# MB1297_MCU2.net
KiCad netlist of a schematic drawn in Altium Designer
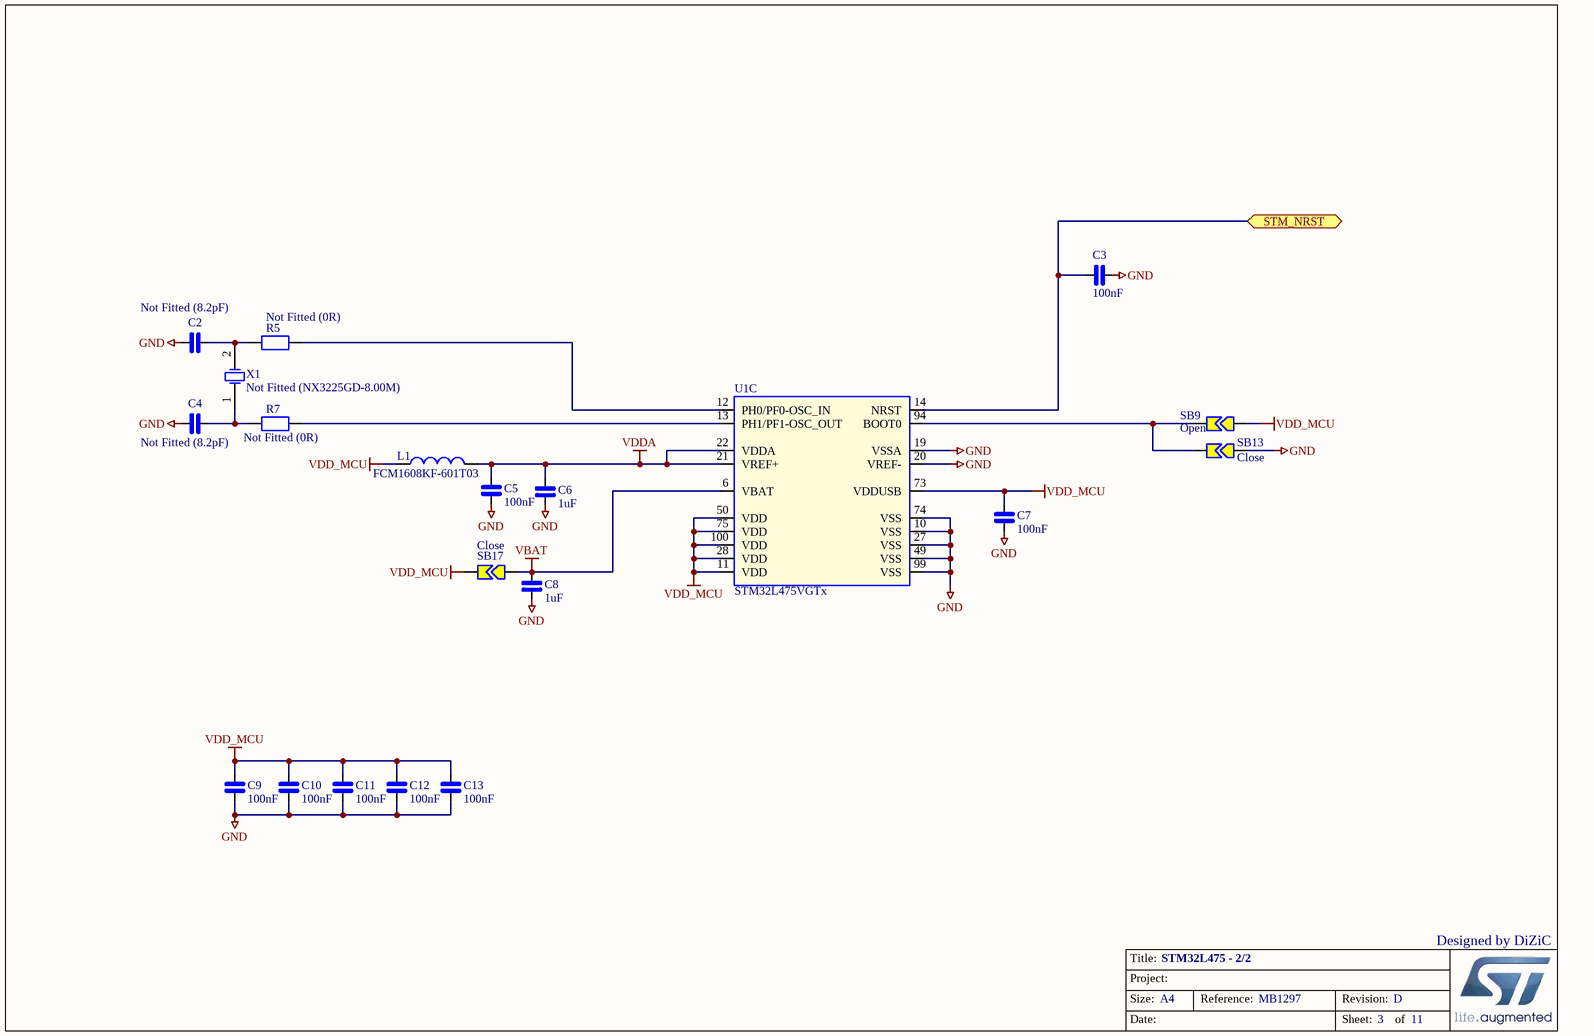
[diagram p0: MB1297_MCU2.SchDoc]

(export (version "E")
  (design (tool "Eeschema 10.0.6"))
  (components
    (comp (ref "C2")
      (value "Not Fitted (8.2pF)")
      (footprint "0402_CAP_NPOL")
      (description "Capacitor_not polarized")
      (libsource (lib "ST_Lib3D") (part "CAP_NPOL"))
    )
    (comp (ref "C3")
      (value "100nF")
      (footprint "0402_CAP_NPOL")
      (description "Capacitor_not polarized")
      (libsource (lib "ST_Lib3D") (part "CAP_NPOL"))
    )
    (comp (ref "C4")
      (value "Not Fitted (8.2pF)")
      (footprint "0402_CAP_NPOL")
      (description "Capacitor_not polarized")
      (libsource (lib "ST_Lib3D") (part "CAP_NPOL"))
    )
    (comp (ref "C5")
      (value "100nF")
      (footprint "0402_CAP_NPOL")
      (description "Capacitor_not polarized")
      (libsource (lib "ST_Lib3D") (part "CAP_NPOL"))
    )
    (comp (ref "C6")
      (value "1uF")
      (footprint "0402_CAP_NPOL")
      (description "Capacitor_not polarized")
      (libsource (lib "ST_Lib3D") (part "CAP_NPOL"))
    )
    (comp (ref "C7")
      (value "100nF")
      (footprint "0402_CAP_NPOL")
      (description "Capacitor_not polarized")
      (libsource (lib "ST_Lib3D") (part "CAP_NPOL"))
    )
    (comp (ref "C8")
      (value "1uF")
      (footprint "0402_CAP_NPOL")
      (description "Capacitor_not polarized")
      (libsource (lib "ST_Lib3D") (part "CAP_NPOL"))
    )
    (comp (ref "C9")
      (value "100nF")
      (footprint "0402_CAP_NPOL")
      (description "Capacitor_not polarized")
      (libsource (lib "MB1297") (part "CAP_NPOL"))
    )
    (comp (ref "C10")
      (value "100nF")
      (footprint "0402_CAP_NPOL")
      (description "Capacitor_not polarized")
      (libsource (lib "MB1297") (part "CAP_NPOL"))
    )
    (comp (ref "C11")
      (value "100nF")
      (footprint "0402_CAP_NPOL")
      (description "Capacitor_not polarized")
      (libsource (lib "MB1297") (part "CAP_NPOL"))
    )
    (comp (ref "C12")
      (value "100nF")
      (footprint "0402_CAP_NPOL")
      (description "Capacitor_not polarized")
      (libsource (lib "MB1297") (part "CAP_NPOL"))
    )
    (comp (ref "C13")
      (value "100nF")
      (footprint "0402_CAP_NPOL")
      (description "Capacitor_not polarized")
      (libsource (lib "MB1297") (part "CAP_NPOL"))
    )
    (comp (ref "L1")
      (value "FCM1608KF-601T03")
      (footprint "0603L")
      (description "Inductor")
      (fields (field (name "PUBLISHER") "Altium Limited"))
      (libsource (lib "Miscellaneous Devices") (part "Inductor"))
    )
    (comp (ref "R5")
      (value "Not Fitted (0R)")
      (footprint "0402_RES")
      (description "Resistor")
      (libsource (lib "Lib3D_Altium10_Schlib") (part "RES"))
    )
    (comp (ref "R7")
      (value "Not Fitted (0R)")
      (footprint "0402_RES")
      (description "Resistor")
      (libsource (lib "Lib3D_Altium10_Schlib") (part "RES"))
    )
    (comp (ref "SB9")
      (value "Open")
      (footprint "SB")
      (description "Solder Jumper")
      (fields (field (name "PUBLISHER") "Altium Limited"))
      (libsource (lib "ST_Lib3D") (part "Strap2"))
    )
    (comp (ref "SB13")
      (value "Close")
      (footprint "SB")
      (description "Solder Jumper")
      (fields (field (name "PUBLISHER") "Altium Limited"))
      (libsource (lib "ST_Lib3D") (part "Strap2"))
    )
    (comp (ref "SB17")
      (value "Close")
      (footprint "SB")
      (description "Solder Jumper")
      (fields (field (name "PUBLISHER") "Altium Limited"))
      (libsource (lib "Lib3D_Altium10_Schlib") (part "Strap2"))
    )
    (comp (ref "U1")
      (value "STM32L475VGTx")
      (footprint "LQFP100 14x14x1.6")
      (libsource (lib "ST_Lib3D") (part "STM32L475VGTx"))
    )
    (comp (ref "X1")
      (value "Not Fitted (NX3225GD-8.00M)")
      (footprint "CRY_NX3225GD_2P")
      (description "Crystal 8Mhz, 8pF, -+50PPM, SMD")
      (libsource (lib "MCD_TEMP_PCH") (part "XTAL_8M_NX3225GD"))
    )
  )
  (nets
    (net (code "1") (name "/STM_NRST") (class "Default")
      (node (ref "C3") (pin "2") (pinfunction "2_2") (pintype "passive"))
      (node (ref "U1") (pin "14") (pinfunction "NRST_14") (pintype "passive"))
    )
    (net (code "2") (name "GND") (class "Default")
      (node (ref "C10") (pin "2") (pinfunction "2_2") (pintype "passive"))
      (node (ref "C11") (pin "2") (pinfunction "2_2") (pintype "passive"))
      (node (ref "C12") (pin "2") (pinfunction "2_2") (pintype "passive"))
      (node (ref "C13") (pin "2") (pinfunction "2_2") (pintype "passive"))
      (node (ref "C2") (pin "2") (pinfunction "2_2") (pintype "passive"))
      (node (ref "C3") (pin "1") (pinfunction "1_1") (pintype "passive"))
      (node (ref "C4") (pin "2") (pinfunction "2_2") (pintype "passive"))
      (node (ref "C5") (pin "2") (pinfunction "2_2") (pintype "passive"))
      (node (ref "C6") (pin "1") (pinfunction "1_1") (pintype "passive"))
      (node (ref "C7") (pin "2") (pinfunction "2_2") (pintype "passive"))
      (node (ref "C8") (pin "1") (pinfunction "1_1") (pintype "passive"))
      (node (ref "C9") (pin "2") (pinfunction "2_2") (pintype "passive"))
      (node (ref "SB13") (pin "1") (pinfunction "1_1") (pintype "passive"))
      (node (ref "U1") (pin "10") (pinfunction "VSS_10") (pintype "passive"))
      (node (ref "U1") (pin "19") (pinfunction "VSSA_19") (pintype "passive"))
      (node (ref "U1") (pin "20") (pinfunction "VREF-_20") (pintype "passive"))
      (node (ref "U1") (pin "27") (pinfunction "VSS_27") (pintype "passive"))
      (node (ref "U1") (pin "49") (pinfunction "VSS_49") (pintype "passive"))
      (node (ref "U1") (pin "74") (pinfunction "VSS_74") (pintype "passive"))
      (node (ref "U1") (pin "99") (pinfunction "VSS_99") (pintype "passive"))
    )
    (net (code "3") (name "Net-(U1C-BOOT0)") (class "Default")
      (node (ref "SB13") (pin "2") (pinfunction "2_2") (pintype "passive"))
      (node (ref "SB9") (pin "2") (pinfunction "2_2") (pintype "passive"))
      (node (ref "U1") (pin "94") (pinfunction "BOOT0_94") (pintype "passive"))
    )
    (net (code "4") (name "Net-(U1C-PH0{slash}PF0-OSC_IN)") (class "Default")
      (node (ref "R5") (pin "1") (pinfunction "1_1") (pintype "passive"))
      (node (ref "U1") (pin "12") (pinfunction "PH0/PF0-OSC_IN_12") (pintype "passive"))
    )
    (net (code "5") (name "Net-(U1C-PH1{slash}PF1-OSC_OUT)") (class "Default")
      (node (ref "R7") (pin "1") (pinfunction "1_1") (pintype "passive"))
      (node (ref "U1") (pin "13") (pinfunction "PH1/PF1-OSC_OUT_13") (pintype "passive"))
    )
    (net (code "6") (name "Net-(X1-OSC1)") (class "Default")
      (node (ref "C4") (pin "1") (pinfunction "1_1") (pintype "passive"))
      (node (ref "R7") (pin "2") (pinfunction "2_2") (pintype "passive"))
      (node (ref "X1") (pin "1") (pinfunction "OSC1_1") (pintype "passive"))
    )
    (net (code "7") (name "Net-(X1-OSC2)") (class "Default")
      (node (ref "C2") (pin "1") (pinfunction "1_1") (pintype "passive"))
      (node (ref "R5") (pin "2") (pinfunction "2_2") (pintype "passive"))
      (node (ref "X1") (pin "2") (pinfunction "OSC2_2") (pintype "passive"))
    )
    (net (code "8") (name "VBAT") (class "Default")
      (node (ref "C8") (pin "2") (pinfunction "2_2") (pintype "passive"))
      (node (ref "SB17") (pin "2") (pinfunction "2_2") (pintype "passive"))
      (node (ref "U1") (pin "6") (pinfunction "VBAT_6") (pintype "passive"))
    )
    (net (code "9") (name "VDDA") (class "Default")
      (node (ref "C5") (pin "1") (pinfunction "1_1") (pintype "passive"))
      (node (ref "C6") (pin "2") (pinfunction "2_2") (pintype "passive"))
      (node (ref "L1") (pin "2") (pinfunction "2_2") (pintype "passive"))
      (node (ref "U1") (pin "21") (pinfunction "VREF+_21") (pintype "passive"))
      (node (ref "U1") (pin "22") (pinfunction "VDDA_22") (pintype "passive"))
    )
    (net (code "10") (name "VDD_MCU") (class "Default")
      (node (ref "C10") (pin "1") (pinfunction "1_1") (pintype "passive"))
      (node (ref "C11") (pin "1") (pinfunction "1_1") (pintype "passive"))
      (node (ref "C12") (pin "1") (pinfunction "1_1") (pintype "passive"))
      (node (ref "C13") (pin "1") (pinfunction "1_1") (pintype "passive"))
      (node (ref "C7") (pin "1") (pinfunction "1_1") (pintype "passive"))
      (node (ref "C9") (pin "1") (pinfunction "1_1") (pintype "passive"))
      (node (ref "L1") (pin "1") (pinfunction "1_1") (pintype "passive"))
      (node (ref "SB17") (pin "1") (pinfunction "1_1") (pintype "passive"))
      (node (ref "SB9") (pin "1") (pinfunction "1_1") (pintype "passive"))
      (node (ref "U1") (pin "100") (pinfunction "VDD_100") (pintype "passive"))
      (node (ref "U1") (pin "11") (pinfunction "VDD_11") (pintype "passive"))
      (node (ref "U1") (pin "28") (pinfunction "VDD_28") (pintype "passive"))
      (node (ref "U1") (pin "50") (pinfunction "VDD_50") (pintype "passive"))
      (node (ref "U1") (pin "73") (pinfunction "VDDUSB_73") (pintype "passive"))
      (node (ref "U1") (pin "75") (pinfunction "VDD_75") (pintype "passive"))
    )
  )
)
